# basler-trigger-shield.net
KiCad netlist of a schematic drawn in EAGLE
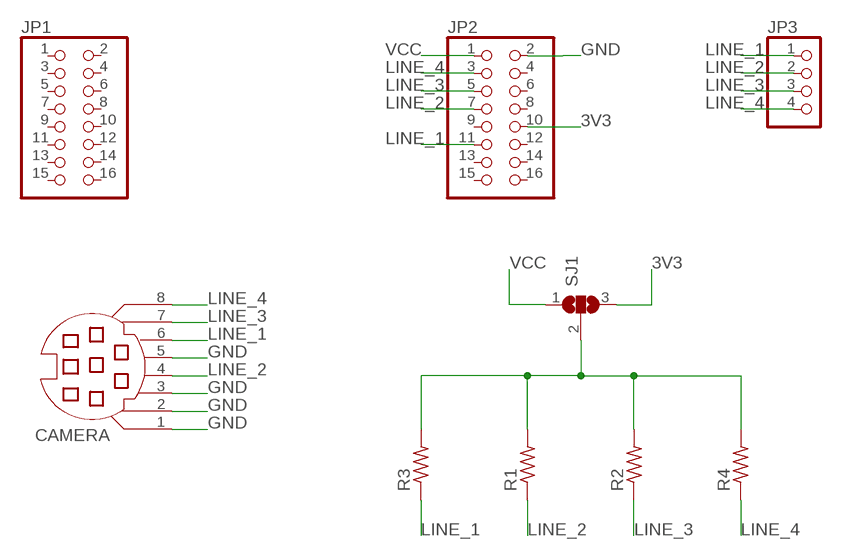
[diagram p0: schematic, sheet 1]

(export (version "E")
  (design (tool "Eeschema 10.0.6"))
  (components
    (comp (ref "CAMERA")
      (value "MD08SS")
      (footprint "eagle-import:MDIN08SS")
      (libsource (lib "eagle-import") (part "MD08SS"))
    )
    (comp (ref "JP1")
      (value "PINHD-2X8")
      (footprint "eagle-import:2X08")
      (libsource (lib "eagle-import") (part "PINHD-2X8"))
    )
    (comp (ref "JP2")
      (value "PINHD-2X8")
      (footprint "eagle-import:2X08")
      (libsource (lib "eagle-import") (part "PINHD-2X8"))
    )
    (comp (ref "JP3")
      (value "PINHD-1X4")
      (footprint "eagle-import:1X04")
      (libsource (lib "eagle-import") (part "PINHD-1X4"))
    )
    (comp (ref "R1")
      (value "R-US_R0603")
      (footprint "eagle-import:R0603")
      (libsource (lib "eagle-import") (part "R-US_R0603"))
    )
    (comp (ref "R2")
      (value "R-US_R0603")
      (footprint "eagle-import:R0603")
      (libsource (lib "eagle-import") (part "R-US_R0603"))
    )
    (comp (ref "R3")
      (value "R-US_R0603")
      (footprint "eagle-import:R0603")
      (libsource (lib "eagle-import") (part "R-US_R0603"))
    )
    (comp (ref "R4")
      (value "R-US_R0603")
      (footprint "eagle-import:R0603")
      (libsource (lib "eagle-import") (part "R-US_R0603"))
    )
    (comp (ref "SJ1")
      (value "SJ2W")
      (footprint "eagle-import:SJ_2")
      (libsource (lib "eagle-import") (part "SJ2W"))
    )
  )
  (nets
    (net (code "1") (name "/3V3") (class "Default")
      (node (ref "JP2") (pin "10") (pinfunction "10_10") (pintype "passive"))
      (node (ref "SJ1") (pin "3") (pinfunction "3_3") (pintype "passive"))
    )
    (net (code "2") (name "/GND") (class "Default")
      (node (ref "CAMERA") (pin "1") (pinfunction "1_1") (pintype "passive"))
      (node (ref "CAMERA") (pin "2") (pinfunction "2_2") (pintype "passive"))
      (node (ref "CAMERA") (pin "3") (pinfunction "3_3") (pintype "passive"))
      (node (ref "CAMERA") (pin "5") (pinfunction "5_5") (pintype "passive"))
      (node (ref "JP2") (pin "2") (pinfunction "2_2") (pintype "passive"))
    )
    (net (code "3") (name "/LINE_1") (class "Default")
      (node (ref "CAMERA") (pin "6") (pinfunction "6_6") (pintype "passive"))
      (node (ref "JP2") (pin "11") (pinfunction "11_11") (pintype "passive"))
      (node (ref "JP3") (pin "1") (pinfunction "1_1") (pintype "passive"))
      (node (ref "R3") (pin "1") (pinfunction "1_1") (pintype "passive"))
    )
    (net (code "4") (name "/LINE_2") (class "Default")
      (node (ref "CAMERA") (pin "4") (pinfunction "4_4") (pintype "passive"))
      (node (ref "JP2") (pin "7") (pinfunction "7_7") (pintype "passive"))
      (node (ref "JP3") (pin "2") (pinfunction "2_2") (pintype "passive"))
      (node (ref "R1") (pin "1") (pinfunction "1_1") (pintype "passive"))
    )
    (net (code "5") (name "/LINE_3") (class "Default")
      (node (ref "CAMERA") (pin "7") (pinfunction "7_7") (pintype "passive"))
      (node (ref "JP2") (pin "5") (pinfunction "5_5") (pintype "passive"))
      (node (ref "JP3") (pin "3") (pinfunction "3_3") (pintype "passive"))
      (node (ref "R2") (pin "1") (pinfunction "1_1") (pintype "passive"))
    )
    (net (code "6") (name "/LINE_4") (class "Default")
      (node (ref "CAMERA") (pin "8") (pinfunction "8_8") (pintype "passive"))
      (node (ref "JP2") (pin "3") (pinfunction "3_3") (pintype "passive"))
      (node (ref "JP3") (pin "4") (pinfunction "4_4") (pintype "passive"))
      (node (ref "R4") (pin "1") (pinfunction "1_1") (pintype "passive"))
    )
    (net (code "7") (name "/VCC") (class "Default")
      (node (ref "JP2") (pin "1") (pinfunction "1_1") (pintype "passive"))
      (node (ref "SJ1") (pin "1") (pinfunction "1_1") (pintype "passive"))
    )
    (net (code "8") (name "Net-(R1-Pad2)") (class "Default")
      (node (ref "R1") (pin "2") (pinfunction "2_2") (pintype "passive"))
      (node (ref "R2") (pin "2") (pinfunction "2_2") (pintype "passive"))
      (node (ref "R3") (pin "2") (pinfunction "2_2") (pintype "passive"))
      (node (ref "R4") (pin "2") (pinfunction "2_2") (pintype "passive"))
      (node (ref "SJ1") (pin "2") (pinfunction "2_2") (pintype "passive"))
    )
    (net (code "9") (name "unconnected-(JP1-Pad1)") (class "Default")
      (node (ref "JP1") (pin "1") (pinfunction "1_1") (pintype "passive"))
    )
    (net (code "10") (name "unconnected-(JP1-Pad2)") (class "Default")
      (node (ref "JP1") (pin "2") (pinfunction "2_2") (pintype "passive"))
    )
    (net (code "11") (name "unconnected-(JP1-Pad3)") (class "Default")
      (node (ref "JP1") (pin "3") (pinfunction "3_3") (pintype "passive"))
    )
    (net (code "12") (name "unconnected-(JP1-Pad4)") (class "Default")
      (node (ref "JP1") (pin "4") (pinfunction "4_4") (pintype "passive"))
    )
    (net (code "13") (name "unconnected-(JP1-Pad5)") (class "Default")
      (node (ref "JP1") (pin "5") (pinfunction "5_5") (pintype "passive"))
    )
    (net (code "14") (name "unconnected-(JP1-Pad6)") (class "Default")
      (node (ref "JP1") (pin "6") (pinfunction "6_6") (pintype "passive"))
    )
    (net (code "15") (name "unconnected-(JP1-Pad7)") (class "Default")
      (node (ref "JP1") (pin "7") (pinfunction "7_7") (pintype "passive"))
    )
    (net (code "16") (name "unconnected-(JP1-Pad8)") (class "Default")
      (node (ref "JP1") (pin "8") (pinfunction "8_8") (pintype "passive"))
    )
    (net (code "17") (name "unconnected-(JP1-Pad9)") (class "Default")
      (node (ref "JP1") (pin "9") (pinfunction "9_9") (pintype "passive"))
    )
    (net (code "18") (name "unconnected-(JP1-Pad10)") (class "Default")
      (node (ref "JP1") (pin "10") (pinfunction "10_10") (pintype "passive"))
    )
    (net (code "19") (name "unconnected-(JP1-Pad11)") (class "Default")
      (node (ref "JP1") (pin "11") (pinfunction "11_11") (pintype "passive"))
    )
    (net (code "20") (name "unconnected-(JP1-Pad12)") (class "Default")
      (node (ref "JP1") (pin "12") (pinfunction "12_12") (pintype "passive"))
    )
    (net (code "21") (name "unconnected-(JP1-Pad13)") (class "Default")
      (node (ref "JP1") (pin "13") (pinfunction "13_13") (pintype "passive"))
    )
    (net (code "22") (name "unconnected-(JP1-Pad14)") (class "Default")
      (node (ref "JP1") (pin "14") (pinfunction "14_14") (pintype "passive"))
    )
    (net (code "23") (name "unconnected-(JP1-Pad15)") (class "Default")
      (node (ref "JP1") (pin "15") (pinfunction "15_15") (pintype "passive"))
    )
    (net (code "24") (name "unconnected-(JP1-Pad16)") (class "Default")
      (node (ref "JP1") (pin "16") (pinfunction "16_16") (pintype "passive"))
    )
    (net (code "25") (name "unconnected-(JP2-Pad4)") (class "Default")
      (node (ref "JP2") (pin "4") (pinfunction "4_4") (pintype "passive"))
    )
    (net (code "26") (name "unconnected-(JP2-Pad6)") (class "Default")
      (node (ref "JP2") (pin "6") (pinfunction "6_6") (pintype "passive"))
    )
    (net (code "27") (name "unconnected-(JP2-Pad8)") (class "Default")
      (node (ref "JP2") (pin "8") (pinfunction "8_8") (pintype "passive"))
    )
    (net (code "28") (name "unconnected-(JP2-Pad9)") (class "Default")
      (node (ref "JP2") (pin "9") (pinfunction "9_9") (pintype "passive"))
    )
    (net (code "29") (name "unconnected-(JP2-Pad12)") (class "Default")
      (node (ref "JP2") (pin "12") (pinfunction "12_12") (pintype "passive"))
    )
    (net (code "30") (name "unconnected-(JP2-Pad13)") (class "Default")
      (node (ref "JP2") (pin "13") (pinfunction "13_13") (pintype "passive"))
    )
    (net (code "31") (name "unconnected-(JP2-Pad14)") (class "Default")
      (node (ref "JP2") (pin "14") (pinfunction "14_14") (pintype "passive"))
    )
    (net (code "32") (name "unconnected-(JP2-Pad15)") (class "Default")
      (node (ref "JP2") (pin "15") (pinfunction "15_15") (pintype "passive"))
    )
    (net (code "33") (name "unconnected-(JP2-Pad16)") (class "Default")
      (node (ref "JP2") (pin "16") (pinfunction "16_16") (pintype "passive"))
    )
  )
)
